# Check_Laser.net
KiCad netlist of a schematic drawn in Altium Designer
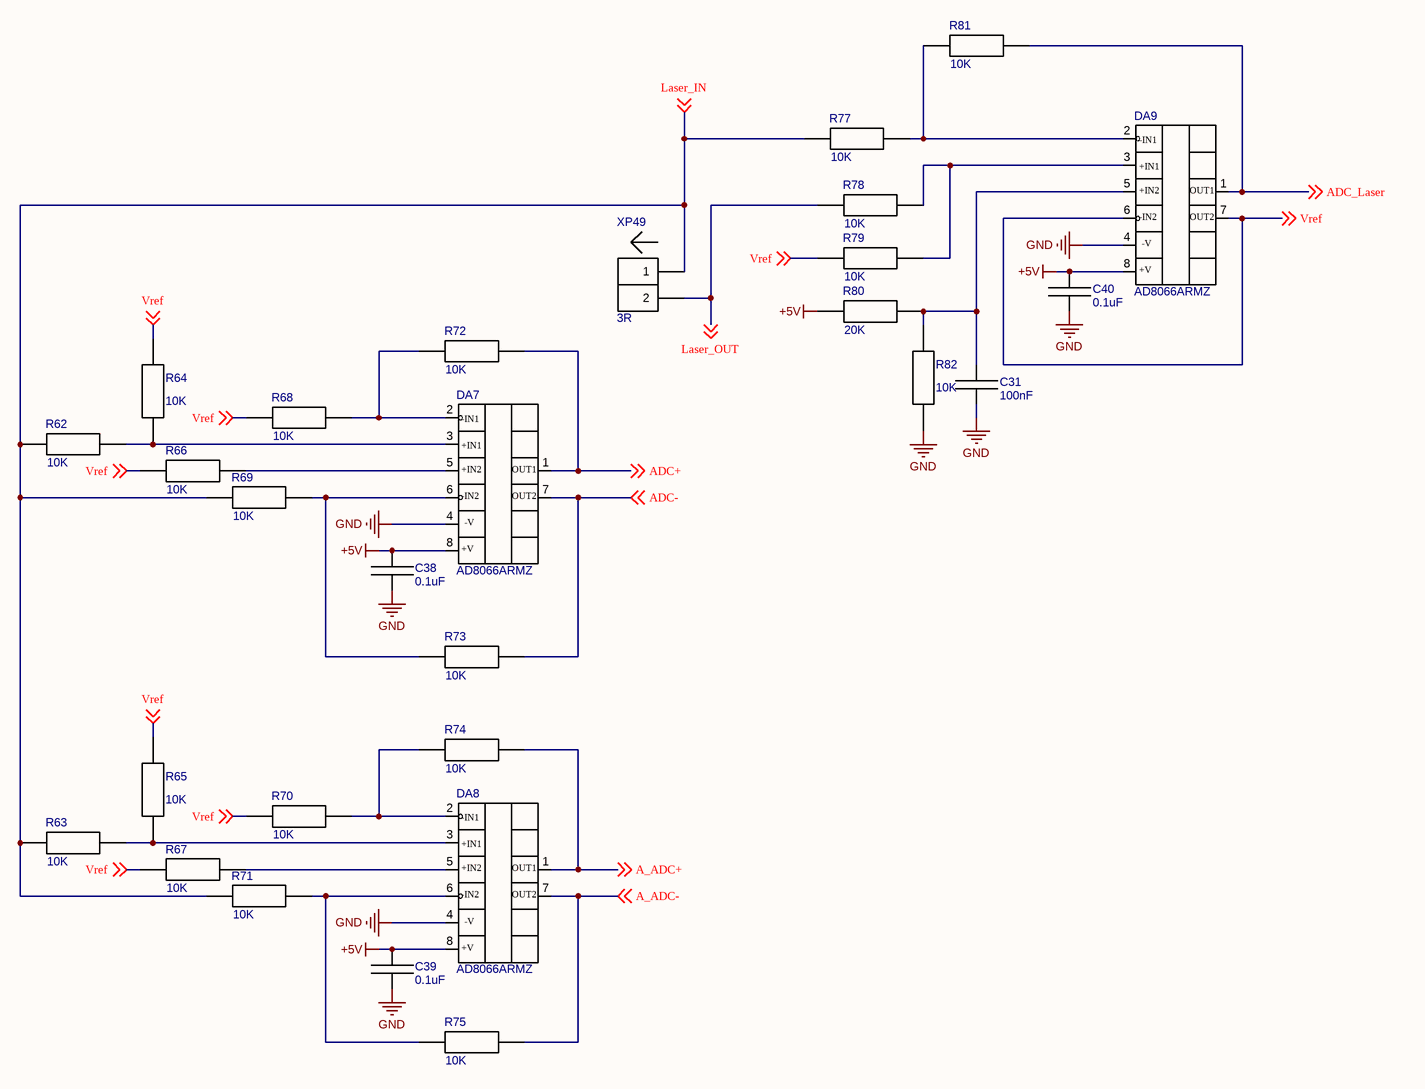
[diagram p0: Check_Laser.SchDoc]

(export (version "E")
  (design (tool "Eeschema 10.0.6"))
  (components
    (comp (ref "C31")
      (value "100nF")
      (footprint "0402C")
      (description "C0402-100nF 10% 50V")
      (fields
        (field (name "PART NUMBER") "SMD CAP CER 100nF ±10% 50V X5R 0402")
        (field (name "ADDED_BY") "Rutel@Mail.ru")
      )
      (libsource (lib "Test_Stand_Pergam") (part "C0402-100nF 10% 50V"))
    )
    (comp (ref "C38")
      (value "0.1uF")
      (footprint "0603C")
      (description "C0603 0.1UF 10% 50V")
      (fields
        (field (name "PART NUMBER") "SMD CAP CER 0.1UF ±10% 50V X7R 0603")
        (field (name "ADDED_BY") "anton@teslatec.ru")
      )
      (libsource (lib "Test_Stand_Pergam") (part "C0603-0.1UF 10% 50V"))
    )
    (comp (ref "C39")
      (value "0.1uF")
      (footprint "0603C")
      (description "C0603 0.1UF 10% 50V")
      (fields
        (field (name "PART NUMBER") "SMD CAP CER 0.1UF ±10% 50V X7R 0603")
        (field (name "ADDED_BY") "anton@teslatec.ru")
      )
      (libsource (lib "Test_Stand_Pergam") (part "C0603-0.1UF 10% 50V"))
    )
    (comp (ref "C40")
      (value "0.1uF")
      (footprint "0603C")
      (description "C0603 0.1UF 10% 50V")
      (fields
        (field (name "PART NUMBER") "SMD CAP CER 0.1UF ±10% 50V X7R 0603")
        (field (name "ADDED_BY") "anton@teslatec.ru")
      )
      (libsource (lib "Test_Stand_Pergam") (part "C0603-0.1UF 10% 50V"))
    )
    (comp (ref "DA7")
      (value "AD8066ARMZ")
      (footprint "MSOP-8")
      (description "High Performance, 145 MHz FastFET Op Amps")
      (fields (field (name "ADDED_BY") "irdolgopolowa@yandex.ru"))
      (libsource (lib "Test_Stand_Pergam") (part "AD8066ARMZ"))
    )
    (comp (ref "DA8")
      (value "AD8066ARMZ")
      (footprint "MSOP-8")
      (description "High Performance, 145 MHz FastFET Op Amps")
      (fields (field (name "ADDED_BY") "irdolgopolowa@yandex.ru"))
      (libsource (lib "Test_Stand_Pergam") (part "AD8066ARMZ"))
    )
    (comp (ref "DA9")
      (value "AD8066ARMZ")
      (footprint "MSOP-8")
      (description "High Performance, 145 MHz FastFET Op Amps")
      (fields (field (name "ADDED_BY") "irdolgopolowa@yandex.ru"))
      (libsource (lib "Test_Stand_Pergam") (part "AD8066ARMZ"))
    )
    (comp (ref "R62")
      (value "10K")
      (footprint "R0402")
      (description "Resistor SMD 10K 1% 0402")
      (fields
        (field (name "PART NUMBER") "SMD RES 10 KOHM 1% ±100ppm/°C 0402")
        (field (name "ADDED_BY") "Rutel@teslatec.ru")
      )
      (libsource (lib "Test_Stand_Pergam") (part "R0402-10K"))
    )
    (comp (ref "R63")
      (value "10K")
      (footprint "R0402")
      (description "Resistor SMD 10K 1% 0402")
      (fields
        (field (name "PART NUMBER") "SMD RES 10 KOHM 1% ±100ppm/°C 0402")
        (field (name "ADDED_BY") "Rutel@teslatec.ru")
      )
      (libsource (lib "Test_Stand_Pergam") (part "R0402-10K"))
    )
    (comp (ref "R64")
      (value "10K")
      (footprint "R0402")
      (description "Resistor SMD 10K 1% 0402")
      (fields
        (field (name "PART NUMBER") "SMD RES 10 KOHM 1% ±100ppm/°C 0402")
        (field (name "ADDED_BY") "Rutel@teslatec.ru")
      )
      (libsource (lib "Test_Stand_Pergam") (part "R0402-10K"))
    )
    (comp (ref "R65")
      (value "10K")
      (footprint "R0402")
      (description "Resistor SMD 10K 1% 0402")
      (fields
        (field (name "PART NUMBER") "SMD RES 10 KOHM 1% ±100ppm/°C 0402")
        (field (name "ADDED_BY") "Rutel@teslatec.ru")
      )
      (libsource (lib "Test_Stand_Pergam") (part "R0402-10K"))
    )
    (comp (ref "R66")
      (value "10K")
      (footprint "R0402")
      (description "Resistor SMD 10K 1% 0402")
      (fields
        (field (name "PART NUMBER") "SMD RES 10 KOHM 1% ±100ppm/°C 0402")
        (field (name "ADDED_BY") "Rutel@teslatec.ru")
      )
      (libsource (lib "Test_Stand_Pergam") (part "R0402-10K"))
    )
    (comp (ref "R67")
      (value "10K")
      (footprint "R0402")
      (description "Resistor SMD 10K 1% 0402")
      (fields
        (field (name "PART NUMBER") "SMD RES 10 KOHM 1% ±100ppm/°C 0402")
        (field (name "ADDED_BY") "Rutel@teslatec.ru")
      )
      (libsource (lib "Test_Stand_Pergam") (part "R0402-10K"))
    )
    (comp (ref "R68")
      (value "10K")
      (footprint "R0402")
      (description "Resistor SMD 10K 1% 0402")
      (fields
        (field (name "PART NUMBER") "SMD RES 10 KOHM 1% ±100ppm/°C 0402")
        (field (name "ADDED_BY") "Rutel@teslatec.ru")
      )
      (libsource (lib "Test_Stand_Pergam") (part "R0402-10K"))
    )
    (comp (ref "R69")
      (value "10K")
      (footprint "R0402")
      (description "Resistor SMD 10K 1% 0402")
      (fields
        (field (name "PART NUMBER") "SMD RES 10 KOHM 1% ±100ppm/°C 0402")
        (field (name "ADDED_BY") "Rutel@teslatec.ru")
      )
      (libsource (lib "Test_Stand_Pergam") (part "R0402-10K"))
    )
    (comp (ref "R70")
      (value "10K")
      (footprint "R0402")
      (description "Resistor SMD 10K 1% 0402")
      (fields
        (field (name "PART NUMBER") "SMD RES 10 KOHM 1% ±100ppm/°C 0402")
        (field (name "ADDED_BY") "Rutel@teslatec.ru")
      )
      (libsource (lib "Test_Stand_Pergam") (part "R0402-10K"))
    )
    (comp (ref "R71")
      (value "10K")
      (footprint "R0402")
      (description "Resistor SMD 10K 1% 0402")
      (fields
        (field (name "PART NUMBER") "SMD RES 10 KOHM 1% ±100ppm/°C 0402")
        (field (name "ADDED_BY") "Rutel@teslatec.ru")
      )
      (libsource (lib "Test_Stand_Pergam") (part "R0402-10K"))
    )
    (comp (ref "R72")
      (value "10K")
      (footprint "R0402")
      (description "Resistor SMD 10K 1% 0402")
      (fields
        (field (name "PART NUMBER") "SMD RES 10 KOHM 1% ±100ppm/°C 0402")
        (field (name "ADDED_BY") "Rutel@teslatec.ru")
      )
      (libsource (lib "Test_Stand_Pergam") (part "R0402-10K"))
    )
    (comp (ref "R73")
      (value "10K")
      (footprint "R0402")
      (description "Resistor SMD 10K 1% 0402")
      (fields
        (field (name "PART NUMBER") "SMD RES 10 KOHM 1% ±100ppm/°C 0402")
        (field (name "ADDED_BY") "Rutel@teslatec.ru")
      )
      (libsource (lib "Test_Stand_Pergam") (part "R0402-10K"))
    )
    (comp (ref "R74")
      (value "10K")
      (footprint "R0402")
      (description "Resistor SMD 10K 1% 0402")
      (fields
        (field (name "PART NUMBER") "SMD RES 10 KOHM 1% ±100ppm/°C 0402")
        (field (name "ADDED_BY") "Rutel@teslatec.ru")
      )
      (libsource (lib "Test_Stand_Pergam") (part "R0402-10K"))
    )
    (comp (ref "R75")
      (value "10K")
      (footprint "R0402")
      (description "Resistor SMD 10K 1% 0402")
      (fields
        (field (name "PART NUMBER") "SMD RES 10 KOHM 1% ±100ppm/°C 0402")
        (field (name "ADDED_BY") "Rutel@teslatec.ru")
      )
      (libsource (lib "Test_Stand_Pergam") (part "R0402-10K"))
    )
    (comp (ref "R77")
      (value "10K")
      (footprint "R0402")
      (description "Resistor SMD 10K 1% 0402")
      (fields
        (field (name "PART NUMBER") "SMD RES 10 KOHM 1% ±100ppm/°C 0402")
        (field (name "ADDED_BY") "Rutel@teslatec.ru")
      )
      (libsource (lib "Test_Stand_Pergam") (part "R0402-10K"))
    )
    (comp (ref "R78")
      (value "10K")
      (footprint "R0402")
      (description "Resistor SMD 10K 1% 0402")
      (fields
        (field (name "PART NUMBER") "SMD RES 10 KOHM 1% ±100ppm/°C 0402")
        (field (name "ADDED_BY") "Rutel@teslatec.ru")
      )
      (libsource (lib "Test_Stand_Pergam") (part "R0402-10K"))
    )
    (comp (ref "R79")
      (value "10K")
      (footprint "R0402")
      (description "Resistor SMD 10K 1% 0402")
      (fields
        (field (name "PART NUMBER") "SMD RES 10 KOHM 1% ±100ppm/°C 0402")
        (field (name "ADDED_BY") "Rutel@teslatec.ru")
      )
      (libsource (lib "Test_Stand_Pergam") (part "R0402-10K"))
    )
    (comp (ref "R80")
      (value "20K")
      (footprint "R0402")
      (description "Resistor SMD 20K 1% 0402")
      (fields
        (field (name "PART NUMBER") "SMD RES 20 KOHM 1% ±100ppm/°C 0402")
        (field (name "ADDED_BY") "Rutel@teslatec.ru")
      )
      (libsource (lib "Test_Stand_Pergam") (part "R0402-20K"))
    )
    (comp (ref "R81")
      (value "10K")
      (footprint "R0402")
      (description "Resistor SMD 10K 1% 0402")
      (fields
        (field (name "PART NUMBER") "SMD RES 10 KOHM 1% ±100ppm/°C 0402")
        (field (name "ADDED_BY") "Rutel@teslatec.ru")
      )
      (libsource (lib "Test_Stand_Pergam") (part "R0402-10K"))
    )
    (comp (ref "R82")
      (value "10K")
      (footprint "R0402")
      (description "Resistor SMD 10K 1% 0402")
      (fields
        (field (name "PART NUMBER") "SMD RES 10 KOHM 1% ±100ppm/°C 0402")
        (field (name "ADDED_BY") "Rutel@teslatec.ru")
      )
      (libsource (lib "Test_Stand_Pergam") (part "R0402-10K"))
    )
    (comp (ref "XP49")
      (value "3R")
      (footprint "PLS-2")
      (description "KNP300JB-52-3R")
      (fields (field (name "PART NUMBER") "PLS-2") (field (name "ADDED_BY") "irdolgopolowa@yandex.ru"))
      (libsource (lib "Test_Stand_Pergam") (part "PLS-2_Laser"))
    )
  )
  (nets
    (net (code "1") (name "+5V") (class "Default")
      (node (ref "C38") (pin "1") (pinfunction "1_1") (pintype "passive"))
      (node (ref "C39") (pin "1") (pinfunction "1_1") (pintype "passive"))
      (node (ref "C40") (pin "1") (pinfunction "1_1") (pintype "passive"))
      (node (ref "DA7") (pin "8") (pinfunction "+VS_8") (pintype "passive"))
      (node (ref "DA8") (pin "8") (pinfunction "+VS_8") (pintype "passive"))
      (node (ref "DA9") (pin "8") (pinfunction "+VS_8") (pintype "passive"))
      (node (ref "R80") (pin "1") (pinfunction "1_1") (pintype "passive"))
    )
    (net (code "2") (name "ADC+") (class "Default")
      (node (ref "DA7") (pin "1") (pinfunction "VOUT_1") (pintype "passive"))
      (node (ref "R72") (pin "2") (pinfunction "2_2") (pintype "passive"))
    )
    (net (code "3") (name "ADC-") (class "Default")
      (node (ref "DA7") (pin "7") (pinfunction "VOUT2_7") (pintype "passive"))
      (node (ref "R73") (pin "2") (pinfunction "2_2") (pintype "passive"))
    )
    (net (code "4") (name "ADC_Laser") (class "Default")
      (node (ref "DA9") (pin "1") (pinfunction "VOUT_1") (pintype "passive"))
      (node (ref "R81") (pin "2") (pinfunction "2_2") (pintype "passive"))
    )
    (net (code "5") (name "A_ADC+") (class "Default")
      (node (ref "DA8") (pin "1") (pinfunction "VOUT_1") (pintype "passive"))
      (node (ref "R74") (pin "2") (pinfunction "2_2") (pintype "passive"))
    )
    (net (code "6") (name "A_ADC-") (class "Default")
      (node (ref "DA8") (pin "7") (pinfunction "VOUT2_7") (pintype "passive"))
      (node (ref "R75") (pin "2") (pinfunction "2_2") (pintype "passive"))
    )
    (net (code "7") (name "GND") (class "Default")
      (node (ref "C31") (pin "1") (pinfunction "1_1") (pintype "passive"))
      (node (ref "C38") (pin "2") (pinfunction "2_2") (pintype "passive"))
      (node (ref "C39") (pin "2") (pinfunction "2_2") (pintype "passive"))
      (node (ref "C40") (pin "2") (pinfunction "2_2") (pintype "passive"))
      (node (ref "DA7") (pin "4") (pinfunction "-VS_4") (pintype "passive"))
      (node (ref "DA8") (pin "4") (pinfunction "-VS_4") (pintype "passive"))
      (node (ref "DA9") (pin "4") (pinfunction "-VS_4") (pintype "passive"))
      (node (ref "R82") (pin "1") (pinfunction "1_1") (pintype "passive"))
    )
    (net (code "8") (name "Laser_IN") (class "Default")
      (node (ref "R62") (pin "1") (pinfunction "1_1") (pintype "passive"))
      (node (ref "R63") (pin "1") (pinfunction "1_1") (pintype "passive"))
      (node (ref "R69") (pin "1") (pinfunction "1_1") (pintype "passive"))
      (node (ref "R71") (pin "1") (pinfunction "1_1") (pintype "passive"))
      (node (ref "R77") (pin "1") (pinfunction "1_1") (pintype "passive"))
      (node (ref "XP49") (pin "1") (pinfunction "1_1") (pintype "passive"))
    )
    (net (code "9") (name "Laser_OUT") (class "Default")
      (node (ref "R78") (pin "1") (pinfunction "1_1") (pintype "passive"))
      (node (ref "XP49") (pin "2") (pinfunction "2_2") (pintype "passive"))
    )
    (net (code "10") (name "Net-(DA7-+IN1)") (class "Default")
      (node (ref "DA7") (pin "3") (pinfunction "+IN1_3") (pintype "passive"))
      (node (ref "R62") (pin "2") (pinfunction "2_2") (pintype "passive"))
      (node (ref "R64") (pin "1") (pinfunction "1_1") (pintype "passive"))
    )
    (net (code "11") (name "Net-(DA7-+IN2)") (class "Default")
      (node (ref "DA7") (pin "5") (pinfunction "+IN2_5") (pintype "passive"))
      (node (ref "R66") (pin "1") (pinfunction "1_1") (pintype "passive"))
    )
    (net (code "12") (name "Net-(DA7--IN1)") (class "Default")
      (node (ref "DA7") (pin "2") (pinfunction "-IN1_2") (pintype "passive"))
      (node (ref "R68") (pin "1") (pinfunction "1_1") (pintype "passive"))
      (node (ref "R72") (pin "1") (pinfunction "1_1") (pintype "passive"))
    )
    (net (code "13") (name "Net-(DA7--IN2)") (class "Default")
      (node (ref "DA7") (pin "6") (pinfunction "-IN2_6") (pintype "passive"))
      (node (ref "R69") (pin "2") (pinfunction "2_2") (pintype "passive"))
      (node (ref "R73") (pin "1") (pinfunction "1_1") (pintype "passive"))
    )
    (net (code "14") (name "Net-(DA8-+IN1)") (class "Default")
      (node (ref "DA8") (pin "3") (pinfunction "+IN1_3") (pintype "passive"))
      (node (ref "R63") (pin "2") (pinfunction "2_2") (pintype "passive"))
      (node (ref "R65") (pin "1") (pinfunction "1_1") (pintype "passive"))
    )
    (net (code "15") (name "Net-(DA8-+IN2)") (class "Default")
      (node (ref "DA8") (pin "5") (pinfunction "+IN2_5") (pintype "passive"))
      (node (ref "R67") (pin "1") (pinfunction "1_1") (pintype "passive"))
    )
    (net (code "16") (name "Net-(DA8--IN1)") (class "Default")
      (node (ref "DA8") (pin "2") (pinfunction "-IN1_2") (pintype "passive"))
      (node (ref "R70") (pin "1") (pinfunction "1_1") (pintype "passive"))
      (node (ref "R74") (pin "1") (pinfunction "1_1") (pintype "passive"))
    )
    (net (code "17") (name "Net-(DA8--IN2)") (class "Default")
      (node (ref "DA8") (pin "6") (pinfunction "-IN2_6") (pintype "passive"))
      (node (ref "R71") (pin "2") (pinfunction "2_2") (pintype "passive"))
      (node (ref "R75") (pin "1") (pinfunction "1_1") (pintype "passive"))
    )
    (net (code "18") (name "Net-(DA9-+IN1)") (class "Default")
      (node (ref "DA9") (pin "3") (pinfunction "+IN1_3") (pintype "passive"))
      (node (ref "R78") (pin "2") (pinfunction "2_2") (pintype "passive"))
      (node (ref "R79") (pin "1") (pinfunction "1_1") (pintype "passive"))
    )
    (net (code "19") (name "Net-(DA9-+IN2)") (class "Default")
      (node (ref "C31") (pin "2") (pinfunction "2_2") (pintype "passive"))
      (node (ref "DA9") (pin "5") (pinfunction "+IN2_5") (pintype "passive"))
      (node (ref "R80") (pin "2") (pinfunction "2_2") (pintype "passive"))
      (node (ref "R82") (pin "2") (pinfunction "2_2") (pintype "passive"))
    )
    (net (code "20") (name "Net-(DA9--IN1)") (class "Default")
      (node (ref "DA9") (pin "2") (pinfunction "-IN1_2") (pintype "passive"))
      (node (ref "R77") (pin "2") (pinfunction "2_2") (pintype "passive"))
      (node (ref "R81") (pin "1") (pinfunction "1_1") (pintype "passive"))
    )
    (net (code "21") (name "Vref") (class "Default")
      (node (ref "DA9") (pin "6") (pinfunction "-IN2_6") (pintype "passive"))
      (node (ref "DA9") (pin "7") (pinfunction "VOUT2_7") (pintype "passive"))
      (node (ref "R64") (pin "2") (pinfunction "2_2") (pintype "passive"))
      (node (ref "R65") (pin "2") (pinfunction "2_2") (pintype "passive"))
      (node (ref "R66") (pin "2") (pinfunction "2_2") (pintype "passive"))
      (node (ref "R67") (pin "2") (pinfunction "2_2") (pintype "passive"))
      (node (ref "R68") (pin "2") (pinfunction "2_2") (pintype "passive"))
      (node (ref "R70") (pin "2") (pinfunction "2_2") (pintype "passive"))
      (node (ref "R79") (pin "2") (pinfunction "2_2") (pintype "passive"))
    )
  )
)
